# atmega328_v1.net
KiCad netlist of a schematic drawn in EAGLE
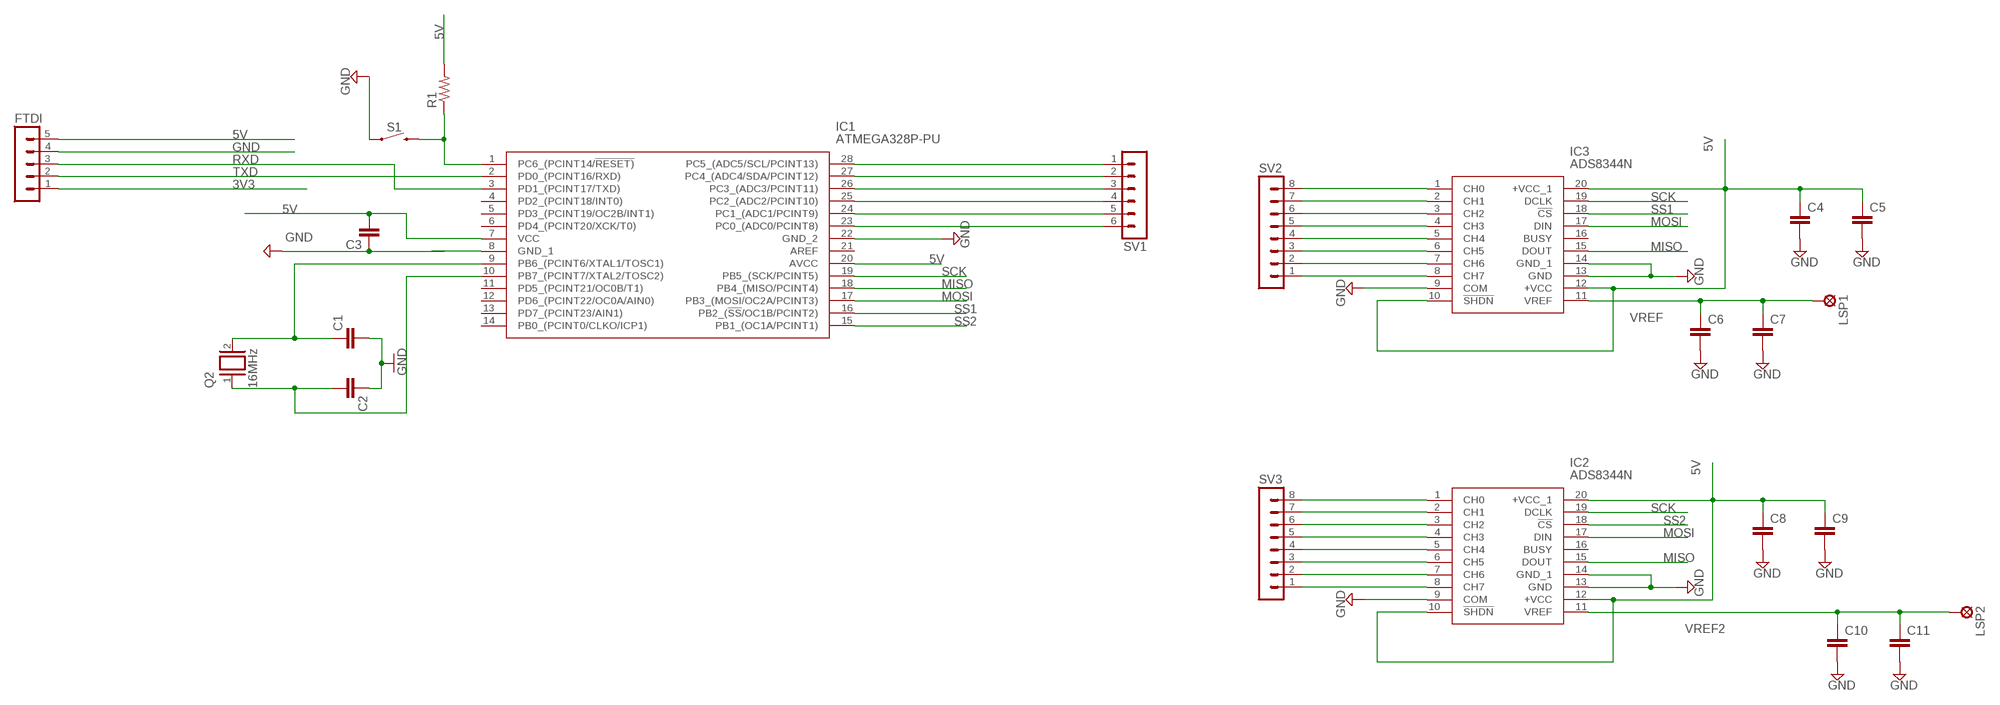
[diagram p0: schematic, sheet 1]

(export (version "E")
  (design (tool "Eeschema 10.0.6"))
  (components
    (comp (ref "C1")
      (value "C-EU025-050X050")
      (footprint "eagle-import:C025-050X050")
      (libsource (lib "eagle-import") (part "C-EU025-050X050"))
    )
    (comp (ref "C2")
      (value "C-EU025-050X050")
      (footprint "eagle-import:C025-050X050")
      (libsource (lib "eagle-import") (part "C-EU025-050X050"))
    )
    (comp (ref "C3")
      (value "C-EU025-050X050")
      (footprint "eagle-import:C025-050X050")
      (libsource (lib "eagle-import") (part "C-EU025-050X050"))
    )
    (comp (ref "C4")
      (value "C-EU050-055X075")
      (footprint "eagle-import:C050-055X075")
      (libsource (lib "eagle-import") (part "C-EU050-055X075"))
    )
    (comp (ref "C5")
      (value "C-EU050-055X075")
      (footprint "eagle-import:C050-055X075")
      (libsource (lib "eagle-import") (part "C-EU050-055X075"))
    )
    (comp (ref "C6")
      (value "C-EU050-055X075")
      (footprint "eagle-import:C050-055X075")
      (libsource (lib "eagle-import") (part "C-EU050-055X075"))
    )
    (comp (ref "C7")
      (value "C-EU050-055X075")
      (footprint "eagle-import:C050-055X075")
      (libsource (lib "eagle-import") (part "C-EU050-055X075"))
    )
    (comp (ref "C8")
      (value "C-EU050-055X075")
      (footprint "eagle-import:C050-055X075")
      (libsource (lib "eagle-import") (part "C-EU050-055X075"))
    )
    (comp (ref "C9")
      (value "C-EU050-055X075")
      (footprint "eagle-import:C050-055X075")
      (libsource (lib "eagle-import") (part "C-EU050-055X075"))
    )
    (comp (ref "C10")
      (value "C-EU050-055X075")
      (footprint "eagle-import:C050-055X075")
      (libsource (lib "eagle-import") (part "C-EU050-055X075"))
    )
    (comp (ref "C11")
      (value "C-EU050-055X075")
      (footprint "eagle-import:C050-055X075")
      (libsource (lib "eagle-import") (part "C-EU050-055X075"))
    )
    (comp (ref "FTDI")
      (value "MA05-1")
      (footprint "eagle-import:MA05-1")
      (libsource (lib "eagle-import") (part "MA05-1"))
    )
    (comp (ref "IC1")
      (value "ATMEGA328P-PU")
      (footprint "eagle-import:DIP794W53P254L3467H457Q28N")
      (fields (field (name "MOUSER_PART_NUMBER") "556-ATMEGA328P-PU"))
      (libsource (lib "eagle-import") (part "ATMEGA328P-PU"))
    )
    (comp (ref "IC2")
      (value "ADS8344N")
      (footprint "eagle-import:SOP65P780X200-20N")
      (fields (field (name "MOUSER_PART_NUMBER") "595-ADS8344N"))
      (libsource (lib "eagle-import") (part "ADS8344N"))
    )
    (comp (ref "IC3")
      (value "ADS8344N")
      (footprint "eagle-import:SOP65P780X200-20N")
      (fields (field (name "MOUSER_PART_NUMBER") "595-ADS8344N"))
      (libsource (lib "eagle-import") (part "ADS8344N"))
    )
    (comp (ref "LSP1")
      (value "SE11")
      (footprint "eagle-import:SE11")
      (libsource (lib "eagle-import") (part "SE11"))
    )
    (comp (ref "LSP2")
      (value "SE11")
      (footprint "eagle-import:SE11")
      (libsource (lib "eagle-import") (part "SE11"))
    )
    (comp (ref "Q2")
      (value "16MHz")
      (footprint "eagle-import:QS")
      (libsource (lib "eagle-import") (part "XTAL/S"))
    )
    (comp (ref "R1")
      (value "R-US_0309/12")
      (footprint "eagle-import:0309_12")
      (libsource (lib "eagle-import") (part "R-US_0309/12"))
    )
    (comp (ref "S1")
      (value "MOMENTARY-SWITCH-SPST-SMD-5.2-REDUNDANT")
      (footprint "eagle-import:TACTILE_SWITCH_SMD_5.2MM")
      (libsource (lib "eagle-import") (part "MOMENTARY-SWITCH-SPST-SMD-5.2-REDUNDANT"))
    )
    (comp (ref "SV1")
      (value "MA06-1")
      (footprint "eagle-import:MA06-1")
      (libsource (lib "eagle-import") (part "MA06-1"))
    )
    (comp (ref "SV2")
      (value "MA08-1")
      (footprint "eagle-import:MA08-1")
      (libsource (lib "eagle-import") (part "MA08-1"))
    )
    (comp (ref "SV3")
      (value "MA08-1")
      (footprint "eagle-import:MA08-1")
      (libsource (lib "eagle-import") (part "MA08-1"))
    )
  )
  (nets
    (net (code "1") (name "/3V3") (class "Default")
      (node (ref "FTDI") (pin "1") (pinfunction "1_1") (pintype "passive"))
    )
    (net (code "2") (name "/5V") (class "Default")
      (node (ref "C3") (pin "2") (pinfunction "2_2") (pintype "passive"))
      (node (ref "C4") (pin "1") (pinfunction "1_1") (pintype "passive"))
      (node (ref "C5") (pin "1") (pinfunction "1_1") (pintype "passive"))
      (node (ref "C8") (pin "1") (pinfunction "1_1") (pintype "passive"))
      (node (ref "C9") (pin "1") (pinfunction "1_1") (pintype "passive"))
      (node (ref "FTDI") (pin "5") (pinfunction "5_5") (pintype "passive"))
      (node (ref "IC1") (pin "20") (pinfunction "AVCC_20") (pintype "bidirectional"))
      (node (ref "IC1") (pin "7") (pinfunction "VCC_7") (pintype "bidirectional"))
      (node (ref "IC2") (pin "10") (pinfunction "~{SHDN}_10") (pintype "bidirectional"))
      (node (ref "IC2") (pin "12") (pinfunction "+VCC_12") (pintype "power_in"))
      (node (ref "IC2") (pin "20") (pinfunction "+VCC_1_20") (pintype "power_in"))
      (node (ref "IC3") (pin "10") (pinfunction "~{SHDN}_10") (pintype "bidirectional"))
      (node (ref "IC3") (pin "12") (pinfunction "+VCC_12") (pintype "power_in"))
      (node (ref "IC3") (pin "20") (pinfunction "+VCC_1_20") (pintype "power_in"))
      (node (ref "R1") (pin "2") (pinfunction "2_2") (pintype "passive"))
    )
    (net (code "3") (name "/MISO") (class "Default")
      (node (ref "IC1") (pin "18") (pinfunction "PB4_(MISO/PCINT4)_18") (pintype "bidirectional"))
      (node (ref "IC2") (pin "15") (pinfunction "DOUT_15") (pintype "output"))
      (node (ref "IC3") (pin "15") (pinfunction "DOUT_15") (pintype "output"))
    )
    (net (code "4") (name "/MOSI") (class "Default")
      (node (ref "IC1") (pin "17") (pinfunction "PB3_(MOSI/OC2A/PCINT3)_17") (pintype "bidirectional"))
      (node (ref "IC2") (pin "17") (pinfunction "DIN_17") (pintype "input"))
      (node (ref "IC3") (pin "17") (pinfunction "DIN_17") (pintype "input"))
    )
    (net (code "5") (name "/RXD") (class "Default")
      (node (ref "FTDI") (pin "3") (pinfunction "3_3") (pintype "passive"))
      (node (ref "IC1") (pin "3") (pinfunction "PD1_(PCINT17/TXD)_3") (pintype "bidirectional"))
    )
    (net (code "6") (name "/SCK") (class "Default")
      (node (ref "IC1") (pin "19") (pinfunction "PB5_(SCK/PCINT5)_19") (pintype "bidirectional"))
      (node (ref "IC2") (pin "19") (pinfunction "DCLK_19") (pintype "input"))
      (node (ref "IC3") (pin "19") (pinfunction "DCLK_19") (pintype "input"))
    )
    (net (code "7") (name "/SS1") (class "Default")
      (node (ref "IC1") (pin "16") (pinfunction "PB2_(~{SS}/OC1B/PCINT2)_16") (pintype "bidirectional"))
      (node (ref "IC3") (pin "18") (pinfunction "~{CS}_18") (pintype "input"))
    )
    (net (code "8") (name "/SS2") (class "Default")
      (node (ref "IC1") (pin "15") (pinfunction "PB1_(OC1A/PCINT1)_15") (pintype "bidirectional"))
      (node (ref "IC2") (pin "18") (pinfunction "~{CS}_18") (pintype "input"))
    )
    (net (code "9") (name "/TXD") (class "Default")
      (node (ref "FTDI") (pin "2") (pinfunction "2_2") (pintype "passive"))
      (node (ref "IC1") (pin "2") (pinfunction "PD0_(PCINT16/RXD)_2") (pintype "bidirectional"))
    )
    (net (code "10") (name "/VREF") (class "Default")
      (node (ref "C6") (pin "1") (pinfunction "1_1") (pintype "passive"))
      (node (ref "C7") (pin "1") (pinfunction "1_1") (pintype "passive"))
      (node (ref "IC3") (pin "11") (pinfunction "VREF_11") (pintype "input"))
      (node (ref "LSP1") (pin "MP") (pinfunction "MP_MP") (pintype "passive"))
    )
    (net (code "11") (name "/VREF2") (class "Default")
      (node (ref "C10") (pin "1") (pinfunction "1_1") (pintype "passive"))
      (node (ref "C11") (pin "1") (pinfunction "1_1") (pintype "passive"))
      (node (ref "IC2") (pin "11") (pinfunction "VREF_11") (pintype "input"))
      (node (ref "LSP2") (pin "MP") (pinfunction "MP_MP") (pintype "passive"))
    )
    (net (code "12") (name "GND") (class "Default")
      (node (ref "C1") (pin "2") (pinfunction "2_2") (pintype "passive"))
      (node (ref "C10") (pin "2") (pinfunction "2_2") (pintype "passive"))
      (node (ref "C11") (pin "2") (pinfunction "2_2") (pintype "passive"))
      (node (ref "C2") (pin "1") (pinfunction "1_1") (pintype "passive"))
      (node (ref "C3") (pin "1") (pinfunction "1_1") (pintype "passive"))
      (node (ref "C4") (pin "2") (pinfunction "2_2") (pintype "passive"))
      (node (ref "C5") (pin "2") (pinfunction "2_2") (pintype "passive"))
      (node (ref "C6") (pin "2") (pinfunction "2_2") (pintype "passive"))
      (node (ref "C7") (pin "2") (pinfunction "2_2") (pintype "passive"))
      (node (ref "C8") (pin "2") (pinfunction "2_2") (pintype "passive"))
      (node (ref "C9") (pin "2") (pinfunction "2_2") (pintype "passive"))
      (node (ref "FTDI") (pin "4") (pinfunction "4_4") (pintype "passive"))
      (node (ref "IC1") (pin "22") (pinfunction "GND_2_22") (pintype "bidirectional"))
      (node (ref "IC2") (pin "13") (pinfunction "GND_13") (pintype "power_in"))
      (node (ref "IC2") (pin "14") (pinfunction "GND_1_14") (pintype "power_in"))
      (node (ref "IC2") (pin "9") (pinfunction "COM_9") (pintype "bidirectional"))
      (node (ref "IC3") (pin "13") (pinfunction "GND_13") (pintype "power_in"))
      (node (ref "IC3") (pin "14") (pinfunction "GND_1_14") (pintype "power_in"))
      (node (ref "IC3") (pin "9") (pinfunction "COM_9") (pintype "bidirectional"))
      (node (ref "S1") (pin "1") (pinfunction "1_1") (pintype "passive"))
      (node (ref "S1") (pin "2") (pinfunction "1_2") (pintype "passive"))
    )
    (net (code "13") (name "Net-(IC1-PB6_(PCINT6{slash}XTAL1{slash}TOSC1))") (class "Default")
      (node (ref "C1") (pin "1") (pinfunction "1_1") (pintype "passive"))
      (node (ref "IC1") (pin "9") (pinfunction "PB6_(PCINT6/XTAL1/TOSC1)_9") (pintype "bidirectional"))
      (node (ref "Q2") (pin "2") (pinfunction "2_2") (pintype "passive"))
    )
    (net (code "14") (name "Net-(IC1-PB7_(PCINT7{slash}XTAL2{slash}TOSC2))") (class "Default")
      (node (ref "C2") (pin "2") (pinfunction "2_2") (pintype "passive"))
      (node (ref "IC1") (pin "10") (pinfunction "PB7_(PCINT7/XTAL2/TOSC2)_10") (pintype "bidirectional"))
      (node (ref "Q2") (pin "1") (pinfunction "1_1") (pintype "passive"))
    )
    (net (code "15") (name "Net-(IC1-PC0_(ADC0{slash}PCINT8))") (class "Default")
      (node (ref "IC1") (pin "23") (pinfunction "PC0_(ADC0/PCINT8)_23") (pintype "bidirectional"))
      (node (ref "SV1") (pin "6") (pinfunction "6_6") (pintype "passive"))
    )
    (net (code "16") (name "Net-(IC1-PC1_(ADC1{slash}PCINT9))") (class "Default")
      (node (ref "IC1") (pin "24") (pinfunction "PC1_(ADC1/PCINT9)_24") (pintype "bidirectional"))
      (node (ref "SV1") (pin "5") (pinfunction "5_5") (pintype "passive"))
    )
    (net (code "17") (name "Net-(IC1-PC2_(ADC2{slash}PCINT10))") (class "Default")
      (node (ref "IC1") (pin "25") (pinfunction "PC2_(ADC2/PCINT10)_25") (pintype "bidirectional"))
      (node (ref "SV1") (pin "4") (pinfunction "4_4") (pintype "passive"))
    )
    (net (code "18") (name "Net-(IC1-PC3_(ADC3{slash}PCINT11))") (class "Default")
      (node (ref "IC1") (pin "26") (pinfunction "PC3_(ADC3/PCINT11)_26") (pintype "bidirectional"))
      (node (ref "SV1") (pin "3") (pinfunction "3_3") (pintype "passive"))
    )
    (net (code "19") (name "Net-(IC1-PC4_(ADC4{slash}SDA{slash}PCINT12))") (class "Default")
      (node (ref "IC1") (pin "27") (pinfunction "PC4_(ADC4/SDA/PCINT12)_27") (pintype "bidirectional"))
      (node (ref "SV1") (pin "2") (pinfunction "2_2") (pintype "passive"))
    )
    (net (code "20") (name "Net-(IC1-PC5_(ADC5{slash}SCL{slash}PCINT13))") (class "Default")
      (node (ref "IC1") (pin "28") (pinfunction "PC5_(ADC5/SCL/PCINT13)_28") (pintype "bidirectional"))
      (node (ref "SV1") (pin "1") (pinfunction "1_1") (pintype "passive"))
    )
    (net (code "21") (name "Net-(IC1-PC6_(PCINT14{slash}~{RESET}))") (class "Default")
      (node (ref "IC1") (pin "1") (pinfunction "PC6_(PCINT14/~{RESET})_1") (pintype "bidirectional"))
      (node (ref "R1") (pin "1") (pinfunction "1_1") (pintype "passive"))
      (node (ref "S1") (pin "3") (pinfunction "2_3") (pintype "passive"))
      (node (ref "S1") (pin "4") (pinfunction "2_4") (pintype "passive"))
    )
    (net (code "22") (name "Net-(IC2-CH0)") (class "Default")
      (node (ref "IC2") (pin "1") (pinfunction "CH0_1") (pintype "bidirectional"))
      (node (ref "SV3") (pin "8") (pinfunction "8_8") (pintype "passive"))
    )
    (net (code "23") (name "Net-(IC2-CH1)") (class "Default")
      (node (ref "IC2") (pin "2") (pinfunction "CH1_2") (pintype "bidirectional"))
      (node (ref "SV3") (pin "7") (pinfunction "7_7") (pintype "passive"))
    )
    (net (code "24") (name "Net-(IC2-CH2)") (class "Default")
      (node (ref "IC2") (pin "3") (pinfunction "CH2_3") (pintype "bidirectional"))
      (node (ref "SV3") (pin "6") (pinfunction "6_6") (pintype "passive"))
    )
    (net (code "25") (name "Net-(IC2-CH3)") (class "Default")
      (node (ref "IC2") (pin "4") (pinfunction "CH3_4") (pintype "bidirectional"))
      (node (ref "SV3") (pin "5") (pinfunction "5_5") (pintype "passive"))
    )
    (net (code "26") (name "Net-(IC2-CH4)") (class "Default")
      (node (ref "IC2") (pin "5") (pinfunction "CH4_5") (pintype "bidirectional"))
      (node (ref "SV3") (pin "4") (pinfunction "4_4") (pintype "passive"))
    )
    (net (code "27") (name "Net-(IC2-CH5)") (class "Default")
      (node (ref "IC2") (pin "6") (pinfunction "CH5_6") (pintype "bidirectional"))
      (node (ref "SV3") (pin "3") (pinfunction "3_3") (pintype "passive"))
    )
    (net (code "28") (name "Net-(IC2-CH6)") (class "Default")
      (node (ref "IC2") (pin "7") (pinfunction "CH6_7") (pintype "bidirectional"))
      (node (ref "SV3") (pin "2") (pinfunction "2_2") (pintype "passive"))
    )
    (net (code "29") (name "Net-(IC2-CH7)") (class "Default")
      (node (ref "IC2") (pin "8") (pinfunction "CH7_8") (pintype "bidirectional"))
      (node (ref "SV3") (pin "1") (pinfunction "1_1") (pintype "passive"))
    )
    (net (code "30") (name "Net-(IC3-CH0)") (class "Default")
      (node (ref "IC3") (pin "1") (pinfunction "CH0_1") (pintype "bidirectional"))
      (node (ref "SV2") (pin "8") (pinfunction "8_8") (pintype "passive"))
    )
    (net (code "31") (name "Net-(IC3-CH1)") (class "Default")
      (node (ref "IC3") (pin "2") (pinfunction "CH1_2") (pintype "bidirectional"))
      (node (ref "SV2") (pin "7") (pinfunction "7_7") (pintype "passive"))
    )
    (net (code "32") (name "Net-(IC3-CH2)") (class "Default")
      (node (ref "IC3") (pin "3") (pinfunction "CH2_3") (pintype "bidirectional"))
      (node (ref "SV2") (pin "6") (pinfunction "6_6") (pintype "passive"))
    )
    (net (code "33") (name "Net-(IC3-CH3)") (class "Default")
      (node (ref "IC3") (pin "4") (pinfunction "CH3_4") (pintype "bidirectional"))
      (node (ref "SV2") (pin "5") (pinfunction "5_5") (pintype "passive"))
    )
    (net (code "34") (name "Net-(IC3-CH4)") (class "Default")
      (node (ref "IC3") (pin "5") (pinfunction "CH4_5") (pintype "bidirectional"))
      (node (ref "SV2") (pin "4") (pinfunction "4_4") (pintype "passive"))
    )
    (net (code "35") (name "Net-(IC3-CH5)") (class "Default")
      (node (ref "IC3") (pin "6") (pinfunction "CH5_6") (pintype "bidirectional"))
      (node (ref "SV2") (pin "3") (pinfunction "3_3") (pintype "passive"))
    )
    (net (code "36") (name "Net-(IC3-CH6)") (class "Default")
      (node (ref "IC3") (pin "7") (pinfunction "CH6_7") (pintype "bidirectional"))
      (node (ref "SV2") (pin "2") (pinfunction "2_2") (pintype "passive"))
    )
    (net (code "37") (name "Net-(IC3-CH7)") (class "Default")
      (node (ref "IC3") (pin "8") (pinfunction "CH7_8") (pintype "bidirectional"))
      (node (ref "SV2") (pin "1") (pinfunction "1_1") (pintype "passive"))
    )
    (net (code "38") (name "unconnected-(IC1-AREF-Pad21)") (class "Default")
      (node (ref "IC1") (pin "21") (pinfunction "AREF_21") (pintype "bidirectional"))
    )
    (net (code "39") (name "unconnected-(IC1-GND_1-Pad8)") (class "Default")
      (node (ref "IC1") (pin "8") (pinfunction "GND_1_8") (pintype "bidirectional"))
    )
    (net (code "40") (name "unconnected-(IC1-PB0_(PCINT0{slash}CLKO{slash}ICP1)-Pad14)") (class "Default")
      (node (ref "IC1") (pin "14") (pinfunction "PB0_(PCINT0/CLKO/ICP1)_14") (pintype "bidirectional"))
    )
    (net (code "41") (name "unconnected-(IC1-PD2_(PCINT18{slash}INT0)-Pad4)") (class "Default")
      (node (ref "IC1") (pin "4") (pinfunction "PD2_(PCINT18/INT0)_4") (pintype "bidirectional"))
    )
    (net (code "42") (name "unconnected-(IC1-PD3_(PCINT19{slash}OC2B{slash}INT1)-Pad5)") (class "Default")
      (node (ref "IC1") (pin "5") (pinfunction "PD3_(PCINT19/OC2B/INT1)_5") (pintype "bidirectional"))
    )
    (net (code "43") (name "unconnected-(IC1-PD4_(PCINT20{slash}XCK{slash}T0)-Pad6)") (class "Default")
      (node (ref "IC1") (pin "6") (pinfunction "PD4_(PCINT20/XCK/T0)_6") (pintype "bidirectional"))
    )
    (net (code "44") (name "unconnected-(IC1-PD5_(PCINT21{slash}OC0B{slash}T1)-Pad11)") (class "Default")
      (node (ref "IC1") (pin "11") (pinfunction "PD5_(PCINT21/OC0B/T1)_11") (pintype "bidirectional"))
    )
    (net (code "45") (name "unconnected-(IC1-PD6_(PCINT22{slash}OC0A{slash}AIN0)-Pad12)") (class "Default")
      (node (ref "IC1") (pin "12") (pinfunction "PD6_(PCINT22/OC0A/AIN0)_12") (pintype "bidirectional"))
    )
    (net (code "46") (name "unconnected-(IC1-PD7_(PCINT23{slash}AIN1)-Pad13)") (class "Default")
      (node (ref "IC1") (pin "13") (pinfunction "PD7_(PCINT23/AIN1)_13") (pintype "bidirectional"))
    )
    (net (code "47") (name "unconnected-(IC2-BUSY-Pad16)") (class "Default")
      (node (ref "IC2") (pin "16") (pinfunction "BUSY_16") (pintype "bidirectional"))
    )
    (net (code "48") (name "unconnected-(IC3-BUSY-Pad16)") (class "Default")
      (node (ref "IC3") (pin "16") (pinfunction "BUSY_16") (pintype "bidirectional"))
    )
  )
)
